# Sheet1.net
KiCad netlist of a schematic drawn in Altium Designer
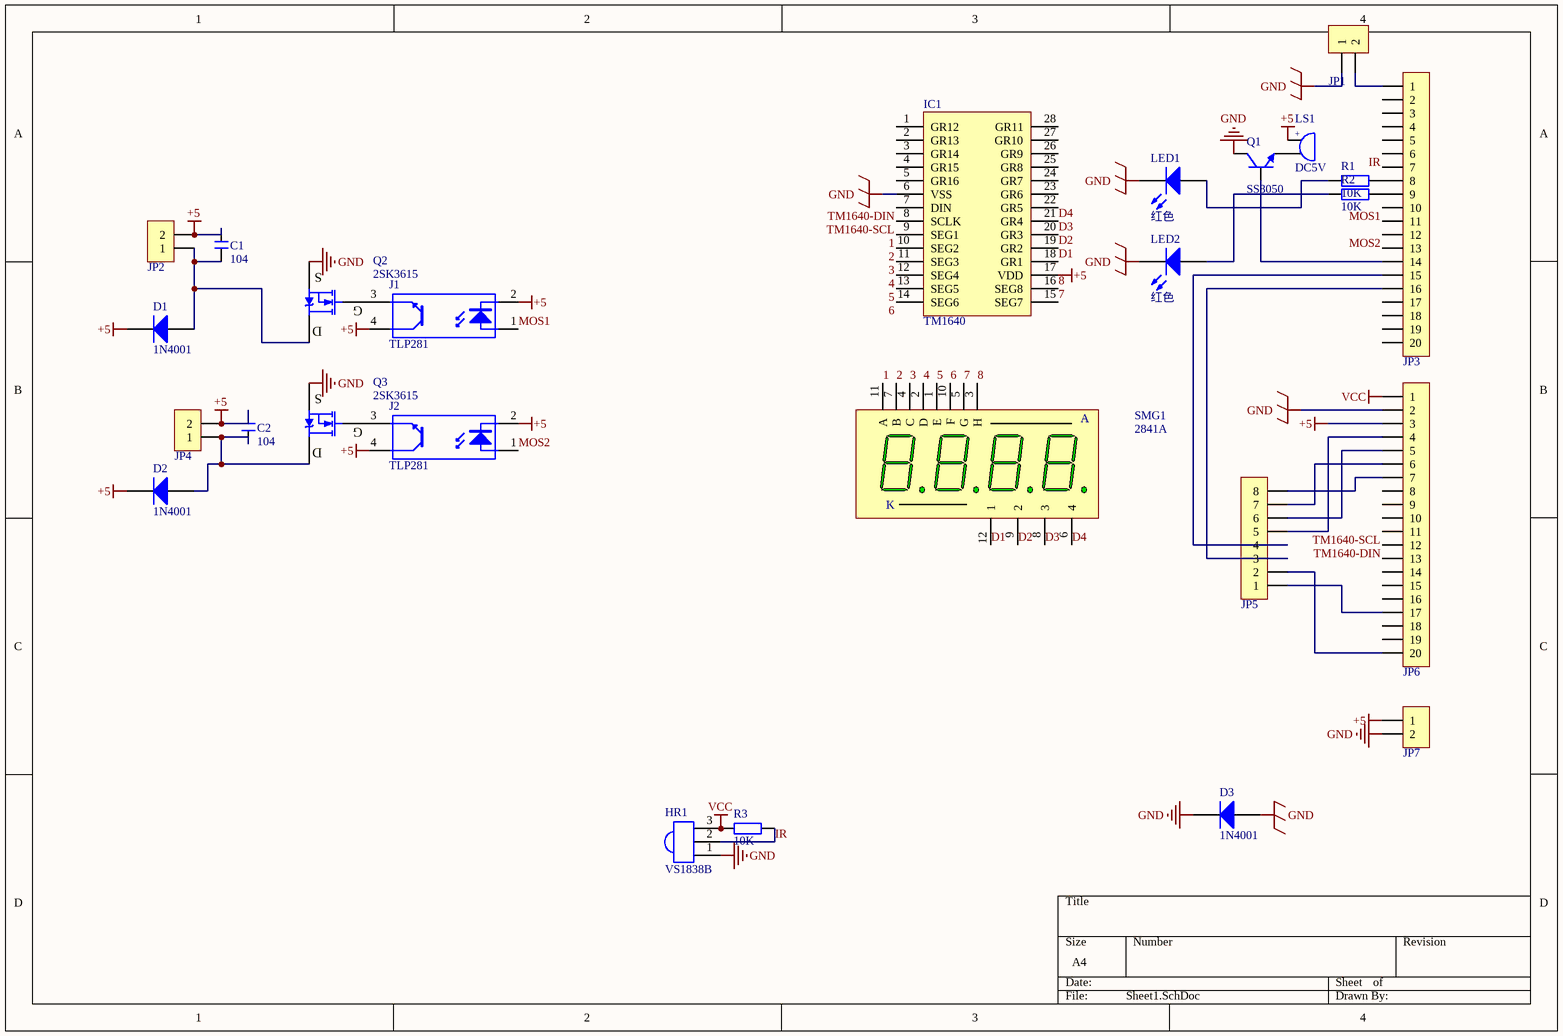
[diagram p0: Sheet1.SchDoc]

(export (version "E")
  (design (tool "Eeschema 10.0.6"))
  (components
    (comp (ref "C1")
      (value "104")
      (footprint "C 0805_L")
      (description "贴片电容")
      (libsource (lib "0.1 - 电阻-电容-电感") (part "C"))
    )
    (comp (ref "C2")
      (value "104")
      (footprint "C 0805_L")
      (description "贴片电容")
      (libsource (lib "0.1 - 电阻-电容-电感") (part "C"))
    )
    (comp (ref "D1")
      (value "Diode")
      (footprint "DIODE-AXL")
      (description "二极管")
      (fields (field (name "TYPE") "1N4001") (field (name "PUBLISHER") "Altium Limited"))
      (libsource (lib "0.2 -  二极管-整流桥") (part "Diode"))
    )
    (comp (ref "D2")
      (value "Diode")
      (footprint "DIODE-AXL")
      (description "二极管")
      (fields (field (name "TYPE") "1N4001") (field (name "PUBLISHER") "Altium Limited"))
      (libsource (lib "0.2 -  二极管-整流桥") (part "Diode"))
    )
    (comp (ref "D3")
      (value "Diode")
      (footprint "DIODE-AXL")
      (description "二极管")
      (fields (field (name "TYPE") "1N4001") (field (name "PUBLISHER") "Altium Limited"))
      (libsource (lib "0.2 -  二极管-整流桥") (part "Diode"))
    )
    (comp (ref "HR1")
      (value "VS1838B")
      (footprint "VS1838B-B")
      (description "红外接收头")
      (fields (field (name "版权归属") "封装库来自淘宝 ID：黄晶宝石"))
      (libsource (lib "1.2 - 传感元件") (part "VS1838B"))
    )
    (comp (ref "IC1")
      (value "TM1640")
      (footprint "SOP28_L")
      (description "LED驱动控制芯片")
      (fields (field (name "版权归属") "封装库来自淘宝 ID：黄晶宝石"))
      (libsource (lib "1.0 - 常见芯片") (part "TM1640"))
    )
    (comp (ref "J1")
      (value "TLP281")
      (footprint "2.50-DIP直插封装:DIP4-300")
      (description "光耦")
      (fields (field (name "PUBLISHER") "Altium Limited"))
      (libsource (lib "2.0 - 保险丝-晶振-光耦") (part "TLP281"))
    )
    (comp (ref "J2")
      (value "TLP281")
      (footprint "2.50-DIP直插封装:DIP4-300")
      (description "光耦")
      (fields (field (name "PUBLISHER") "Altium Limited"))
      (libsource (lib "2.0 - 保险丝-晶振-光耦") (part "TLP281"))
    )
    (comp (ref "JP1")
      (value "HDR-1X2")
      (footprint "HDR2.54-LI-2P")
      (description "2P接插件")
      (fields (field (name "版权归属") "封装库来自淘宝 ID：黄晶宝石"))
      (libsource (lib "5.3 - 接插件-脚距2.54 (100mil) ") (part "Header 2"))
    )
    (comp (ref "JP2")
      (value "HDR-1X2")
      (footprint "KF2EDGK5.08-LI-2P")
      (description "2P接插件")
      (fields (field (name "版权归属") "封装库来自淘宝卖家 ID：黄晶宝石"))
      (libsource (lib "") (part "Header 2_1"))
    )
    (comp (ref "JP3")
      (value "HDR-1X20")
      (footprint "HDR2.54-M-LI-20P")
      (description "20P接插件")
      (fields (field (name "版权归属") "封装库来自淘宝 ID：黄晶宝石"))
      (libsource (lib "5.3 - 接插件-脚距2.54 (100mil) ") (part "Header 20"))
    )
    (comp (ref "JP4")
      (value "HDR-1X2")
      (footprint "KF2EDGK5.08-LI-2P")
      (description "2P接插件")
      (fields (field (name "版权归属") "封装库来自淘宝卖家 ID：黄晶宝石"))
      (libsource (lib "") (part "Header 2_1"))
    )
    (comp (ref "JP5")
      (value "HDR-1X8")
      (footprint "HDR2.54-M-LI-8P")
      (description "8P接插件")
      (fields (field (name "版权归属") "封装库来自淘宝 ID：黄晶宝石"))
      (libsource (lib "5.3 - 接插件-脚距2.54 (100mil) ") (part "Header 8"))
    )
    (comp (ref "JP6")
      (value "HDR-1X20")
      (footprint "HDR2.54-M-LI-20P")
      (description "20P接插件")
      (fields (field (name "版权归属") "封装库来自淘宝 ID：黄晶宝石"))
      (libsource (lib "5.3 - 接插件-脚距2.54 (100mil) ") (part "Header 20"))
    )
    (comp (ref "JP7")
      (value "HDR-1X2")
      (footprint "KF2EDGK5.08-LI-2P")
      (description "2P接插件")
      (fields (field (name "版权归属") "封装库来自淘宝卖家 ID：黄晶宝石"))
      (libsource (lib "5.8 - 接插件-脚距5.08 (200mil) ") (part "Header 2"))
    )
    (comp (ref "LED1")
      (value "红色")
      (footprint "LED 3MM-B")
      (description "直插3mm LED")
      (fields (field (name "版权归属") "封装库来自淘宝 ID：黄晶宝石"))
      (libsource (lib "0.3 - LED发光二极管") (part "LED-3MM"))
    )
    (comp (ref "LED2")
      (value "红色")
      (footprint "LED 3MM-B")
      (description "直插3mm LED")
      (fields (field (name "版权归属") "封装库来自淘宝 ID：黄晶宝石"))
      (libsource (lib "0.3 - LED发光二极管") (part "LED-3MM"))
    )
    (comp (ref "LS1")
      (value "DC5V")
      (footprint "BEEP 5x9x5.5")
      (description "蜂鸣器")
      (fields (field (name "版权归属") "封装库来自淘宝 ID：黄晶宝石"))
      (libsource (lib "4.1 - 未分类器件") (part "BEEP"))
    )
    (comp (ref "Q1")
      (value "SS8050")
      (footprint "TO92A")
      (description "高频放大-NPN型")
      (fields (field (name "版权归属") "封装库来自淘宝 ID：黄晶宝石"))
      (libsource (lib "0.4 - 三极管") (part "8050-DIP"))
    )
    (comp (ref "Q2")
      (value "2SK3615")
      (footprint "TO252")
      (description "N沟场效应管")
      (libsource (lib "0.5 - 场效应管-可控硅") (part "2SK3615"))
    )
    (comp (ref "Q3")
      (value "2SK3615")
      (footprint "TO252")
      (description "N沟场效应管")
      (libsource (lib "0.5 - 场效应管-可控硅") (part "2SK3615"))
    )
    (comp (ref "R1")
      (value "10K")
      (footprint "R 0805_L")
      (description "贴片电阻")
      (fields (field (name "版权归属") "来自淘宝 ID：黄晶宝石"))
      (libsource (lib "0.1 - 电阻-电容-电感") (part "R"))
    )
    (comp (ref "R2")
      (value "10K")
      (footprint "R 0805_L")
      (description "贴片电阻")
      (fields (field (name "版权归属") "来自淘宝 ID：黄晶宝石"))
      (libsource (lib "0.1 - 电阻-电容-电感") (part "R"))
    )
    (comp (ref "R3")
      (value "10K")
      (footprint "R 0805_L")
      (description "贴片电阻")
      (fields (field (name "版权归属") "来自淘宝 ID：黄晶宝石"))
      (libsource (lib "0.1 - 电阻-电容-电感") (part "R"))
    )
    (comp (ref "SMG1")
      (value "2841A")
      (footprint "SMG 0.28-4P_B")
      (description "0.28寸4位共阴数码管")
      (fields (field (name "版权归属") "封装库来自淘宝 ID：黄晶宝石"))
      (libsource (lib "0.6 - 数码管-TFT屏") (part "2841A"))
    )
  )
  (nets
    (net (code "1") (name "+5") (class "Default")
      (node (ref "C1") (pin "2") (pinfunction "2_2") (pintype "passive"))
      (node (ref "C2") (pin "2") (pinfunction "2_2") (pintype "passive"))
      (node (ref "D1") (pin "2") (pinfunction "K_2") (pintype "passive"))
      (node (ref "D2") (pin "2") (pinfunction "K_2") (pintype "passive"))
      (node (ref "IC1") (pin "17") (pinfunction "VDD_17") (pintype "passive"))
      (node (ref "J1") (pin "2") (pinfunction "K_2") (pintype "passive"))
      (node (ref "J1") (pin "4") (pinfunction "C_4") (pintype "passive"))
      (node (ref "J2") (pin "2") (pinfunction "K_2") (pintype "passive"))
      (node (ref "J2") (pin "4") (pinfunction "C_4") (pintype "passive"))
      (node (ref "JP2") (pin "2") (pinfunction "2_2") (pintype "passive"))
      (node (ref "JP4") (pin "2") (pinfunction "2_2") (pintype "passive"))
      (node (ref "JP6") (pin "3") (pinfunction "3_3") (pintype "passive"))
      (node (ref "JP7") (pin "1") (pinfunction "1_1") (pintype "passive"))
      (node (ref "LS1") (pin "1") (pinfunction "1_1") (pintype "passive"))
    )
    (net (code "2") (name "/1") (class "Default")
      (node (ref "IC1") (pin "9") (pinfunction "SEG1_9") (pintype "passive"))
      (node (ref "SMG1") (pin "11") (pinfunction "A_11") (pintype "passive"))
    )
    (net (code "3") (name "/2") (class "Default")
      (node (ref "IC1") (pin "10") (pinfunction "SEG2_10") (pintype "passive"))
      (node (ref "SMG1") (pin "7") (pinfunction "B_7") (pintype "passive"))
    )
    (net (code "4") (name "/3") (class "Default")
      (node (ref "IC1") (pin "11") (pinfunction "SEG3_11") (pintype "passive"))
      (node (ref "SMG1") (pin "4") (pinfunction "C_4") (pintype "passive"))
    )
    (net (code "5") (name "/4") (class "Default")
      (node (ref "IC1") (pin "12") (pinfunction "SEG4_12") (pintype "passive"))
      (node (ref "SMG1") (pin "2") (pinfunction "D_2") (pintype "passive"))
    )
    (net (code "6") (name "/5") (class "Default")
      (node (ref "IC1") (pin "13") (pinfunction "SEG5_13") (pintype "passive"))
      (node (ref "SMG1") (pin "1") (pinfunction "E_1") (pintype "passive"))
    )
    (net (code "7") (name "/6") (class "Default")
      (node (ref "IC1") (pin "14") (pinfunction "SEG6_14") (pintype "passive"))
      (node (ref "SMG1") (pin "10") (pinfunction "F_10") (pintype "passive"))
    )
    (net (code "8") (name "/7") (class "Default")
      (node (ref "IC1") (pin "15") (pinfunction "SEG7_15") (pintype "passive"))
      (node (ref "SMG1") (pin "5") (pinfunction "G_5") (pintype "passive"))
    )
    (net (code "9") (name "/8") (class "Default")
      (node (ref "IC1") (pin "16") (pinfunction "SEG8_16") (pintype "passive"))
      (node (ref "SMG1") (pin "3") (pinfunction "H_3") (pintype "passive"))
    )
    (net (code "10") (name "/D1") (class "Default")
      (node (ref "IC1") (pin "18") (pinfunction "GR1_18") (pintype "passive"))
      (node (ref "SMG1") (pin "12") (pinfunction "1_12") (pintype "passive"))
    )
    (net (code "11") (name "/D2") (class "Default")
      (node (ref "IC1") (pin "19") (pinfunction "GR2_19") (pintype "passive"))
      (node (ref "SMG1") (pin "9") (pinfunction "2_9") (pintype "passive"))
    )
    (net (code "12") (name "/D3") (class "Default")
      (node (ref "IC1") (pin "20") (pinfunction "GR3_20") (pintype "passive"))
      (node (ref "SMG1") (pin "8") (pinfunction "3_8") (pintype "passive"))
    )
    (net (code "13") (name "/D4") (class "Default")
      (node (ref "IC1") (pin "21") (pinfunction "GR4_21") (pintype "passive"))
      (node (ref "SMG1") (pin "6") (pinfunction "4_6") (pintype "passive"))
    )
    (net (code "14") (name "/IR") (class "Default")
      (node (ref "HR1") (pin "2") (pinfunction "K_2") (pintype "passive"))
      (node (ref "JP3") (pin "6") (pinfunction "6_6") (pintype "passive"))
      (node (ref "R3") (pin "2") (pinfunction "2_2") (pintype "passive"))
    )
    (net (code "15") (name "/MOS1") (class "Default")
      (node (ref "J1") (pin "1") (pinfunction "A_1") (pintype "passive"))
      (node (ref "JP3") (pin "10") (pinfunction "10_10") (pintype "passive"))
    )
    (net (code "16") (name "/MOS2") (class "Default")
      (node (ref "J2") (pin "1") (pinfunction "A_1") (pintype "passive"))
      (node (ref "JP3") (pin "12") (pinfunction "12_12") (pintype "passive"))
    )
    (net (code "17") (name "/TM1640-DIN") (class "Default")
      (node (ref "IC1") (pin "7") (pinfunction "DIN_7") (pintype "passive"))
      (node (ref "JP6") (pin "12") (pinfunction "12_12") (pintype "passive"))
    )
    (net (code "18") (name "/TM1640-SCL") (class "Default")
      (node (ref "IC1") (pin "8") (pinfunction "SCLK_8") (pintype "passive"))
      (node (ref "JP6") (pin "11") (pinfunction "11_11") (pintype "passive"))
    )
    (net (code "19") (name "GND") (class "Default")
      (node (ref "D3") (pin "1") (pinfunction "A_1") (pintype "passive"))
      (node (ref "D3") (pin "2") (pinfunction "K_2") (pintype "passive"))
      (node (ref "HR1") (pin "1") (pinfunction "A_1") (pintype "passive"))
      (node (ref "IC1") (pin "6") (pinfunction "VSS_6") (pintype "passive"))
      (node (ref "JP1") (pin "1") (pinfunction "1_1") (pintype "passive"))
      (node (ref "JP6") (pin "2") (pinfunction "2_2") (pintype "passive"))
      (node (ref "JP7") (pin "2") (pinfunction "2_2") (pintype "passive"))
      (node (ref "LED1") (pin "2") (pinfunction "K_2") (pintype "passive"))
      (node (ref "LED2") (pin "2") (pinfunction "K_2") (pintype "passive"))
      (node (ref "Q1") (pin "3") (pinfunction "C_3") (pintype "passive"))
      (node (ref "Q2") (pin "3") (pinfunction "S_3") (pintype "passive"))
      (node (ref "Q3") (pin "3") (pinfunction "S_3") (pintype "passive"))
    )
    (net (code "20") (name "Net-(D1-A)") (class "Default")
      (node (ref "C1") (pin "1") (pinfunction "1_1") (pintype "passive"))
      (node (ref "D1") (pin "1") (pinfunction "A_1") (pintype "passive"))
      (node (ref "JP2") (pin "1") (pinfunction "1_1") (pintype "passive"))
      (node (ref "Q2") (pin "2") (pinfunction "D_2") (pintype "passive"))
    )
    (net (code "21") (name "Net-(D2-A)") (class "Default")
      (node (ref "C2") (pin "1") (pinfunction "1_1") (pintype "passive"))
      (node (ref "D2") (pin "1") (pinfunction "A_1") (pintype "passive"))
      (node (ref "JP4") (pin "1") (pinfunction "1_1") (pintype "passive"))
      (node (ref "Q3") (pin "2") (pinfunction "D_2") (pintype "passive"))
    )
    (net (code "22") (name "Net-(J1-E)") (class "Default")
      (node (ref "J1") (pin "3") (pinfunction "E_3") (pintype "passive"))
      (node (ref "Q2") (pin "1") (pinfunction "G_1") (pintype "passive"))
    )
    (net (code "23") (name "Net-(J2-E)") (class "Default")
      (node (ref "J2") (pin "3") (pinfunction "E_3") (pintype "passive"))
      (node (ref "Q3") (pin "1") (pinfunction "G_1") (pintype "passive"))
    )
    (net (code "24") (name "Net-(JP1-Pad2)") (class "Default")
      (node (ref "JP1") (pin "2") (pinfunction "2_2") (pintype "passive"))
      (node (ref "JP3") (pin "1") (pinfunction "1_1") (pintype "passive"))
    )
    (net (code "25") (name "Net-(JP3-Pad8)") (class "Default")
      (node (ref "JP3") (pin "8") (pinfunction "8_8") (pintype "passive"))
      (node (ref "R1") (pin "2") (pinfunction "2_2") (pintype "passive"))
    )
    (net (code "26") (name "Net-(JP3-Pad9)") (class "Default")
      (node (ref "JP3") (pin "9") (pinfunction "9_9") (pintype "passive"))
      (node (ref "R2") (pin "2") (pinfunction "2_2") (pintype "passive"))
    )
    (net (code "27") (name "Net-(JP3-Pad15)") (class "Default")
      (node (ref "JP3") (pin "15") (pinfunction "15_15") (pintype "passive"))
      (node (ref "JP5") (pin "4") (pinfunction "4_4") (pintype "passive"))
    )
    (net (code "28") (name "Net-(JP3-Pad16)") (class "Default")
      (node (ref "JP3") (pin "16") (pinfunction "16_16") (pintype "passive"))
      (node (ref "JP5") (pin "3") (pinfunction "3_3") (pintype "passive"))
    )
    (net (code "29") (name "Net-(JP5-Pad1)") (class "Default")
      (node (ref "JP5") (pin "1") (pinfunction "1_1") (pintype "passive"))
      (node (ref "JP6") (pin "17") (pinfunction "17_17") (pintype "passive"))
    )
    (net (code "30") (name "Net-(JP5-Pad2)") (class "Default")
      (node (ref "JP5") (pin "2") (pinfunction "2_2") (pintype "passive"))
      (node (ref "JP6") (pin "20") (pinfunction "20_20") (pintype "passive"))
    )
    (net (code "31") (name "Net-(JP5-Pad5)") (class "Default")
      (node (ref "JP5") (pin "5") (pinfunction "5_5") (pintype "passive"))
      (node (ref "JP6") (pin "4") (pinfunction "4_4") (pintype "passive"))
    )
    (net (code "32") (name "Net-(JP5-Pad6)") (class "Default")
      (node (ref "JP5") (pin "6") (pinfunction "6_6") (pintype "passive"))
      (node (ref "JP6") (pin "5") (pinfunction "5_5") (pintype "passive"))
    )
    (net (code "33") (name "Net-(JP5-Pad7)") (class "Default")
      (node (ref "JP5") (pin "7") (pinfunction "7_7") (pintype "passive"))
      (node (ref "JP6") (pin "6") (pinfunction "6_6") (pintype "passive"))
    )
    (net (code "34") (name "Net-(JP5-Pad8)") (class "Default")
      (node (ref "JP5") (pin "8") (pinfunction "8_8") (pintype "passive"))
      (node (ref "JP6") (pin "7") (pinfunction "7_7") (pintype "passive"))
    )
    (net (code "35") (name "Net-(LED1-A)") (class "Default")
      (node (ref "LED1") (pin "1") (pinfunction "A_1") (pintype "passive"))
      (node (ref "R1") (pin "1") (pinfunction "1_1") (pintype "passive"))
    )
    (net (code "36") (name "Net-(LED2-A)") (class "Default")
      (node (ref "LED2") (pin "1") (pinfunction "A_1") (pintype "passive"))
      (node (ref "R2") (pin "1") (pinfunction "1_1") (pintype "passive"))
    )
    (net (code "37") (name "Net-(Q1-B)") (class "Default")
      (node (ref "JP3") (pin "14") (pinfunction "14_14") (pintype "passive"))
      (node (ref "Q1") (pin "2") (pinfunction "B_2") (pintype "passive"))
    )
    (net (code "38") (name "Net-(Q1-E)") (class "Default")
      (node (ref "LS1") (pin "2") (pinfunction "2_2") (pintype "passive"))
      (node (ref "Q1") (pin "1") (pinfunction "E_1") (pintype "passive"))
    )
    (net (code "39") (name "VCC") (class "Default")
      (node (ref "HR1") (pin "3") (pinfunction "E_3") (pintype "passive"))
      (node (ref "JP6") (pin "1") (pinfunction "1_1") (pintype "passive"))
      (node (ref "R3") (pin "1") (pinfunction "1_1") (pintype "passive"))
    )
    (net (code "40") (name "unconnected-(IC1-GR5-Pad22)") (class "Default")
      (node (ref "IC1") (pin "22") (pinfunction "GR5_22") (pintype "passive"))
    )
    (net (code "41") (name "unconnected-(IC1-GR6-Pad23)") (class "Default")
      (node (ref "IC1") (pin "23") (pinfunction "GR6_23") (pintype "passive"))
    )
    (net (code "42") (name "unconnected-(IC1-GR7-Pad24)") (class "Default")
      (node (ref "IC1") (pin "24") (pinfunction "GR7_24") (pintype "passive"))
    )
    (net (code "43") (name "unconnected-(IC1-GR8-Pad25)") (class "Default")
      (node (ref "IC1") (pin "25") (pinfunction "GR8_25") (pintype "passive"))
    )
    (net (code "44") (name "unconnected-(IC1-GR9-Pad26)") (class "Default")
      (node (ref "IC1") (pin "26") (pinfunction "GR9_26") (pintype "passive"))
    )
    (net (code "45") (name "unconnected-(IC1-GR10-Pad27)") (class "Default")
      (node (ref "IC1") (pin "27") (pinfunction "GR10_27") (pintype "passive"))
    )
    (net (code "46") (name "unconnected-(IC1-GR11-Pad28)") (class "Default")
      (node (ref "IC1") (pin "28") (pinfunction "GR11_28") (pintype "passive"))
    )
    (net (code "47") (name "unconnected-(IC1-GR12-Pad1)") (class "Default")
      (node (ref "IC1") (pin "1") (pinfunction "GR12_1") (pintype "passive"))
    )
    (net (code "48") (name "unconnected-(IC1-GR13-Pad2)") (class "Default")
      (node (ref "IC1") (pin "2") (pinfunction "GR13_2") (pintype "passive"))
    )
    (net (code "49") (name "unconnected-(IC1-GR14-Pad3)") (class "Default")
      (node (ref "IC1") (pin "3") (pinfunction "GR14_3") (pintype "passive"))
    )
    (net (code "50") (name "unconnected-(IC1-GR15-Pad4)") (class "Default")
      (node (ref "IC1") (pin "4") (pinfunction "GR15_4") (pintype "passive"))
    )
    (net (code "51") (name "unconnected-(IC1-GR16-Pad5)") (class "Default")
      (node (ref "IC1") (pin "5") (pinfunction "GR16_5") (pintype "passive"))
    )
    (net (code "52") (name "unconnected-(JP3-Pad2)") (class "Default")
      (node (ref "JP3") (pin "2") (pinfunction "2_2") (pintype "passive"))
    )
    (net (code "53") (name "unconnected-(JP3-Pad3)") (class "Default")
      (node (ref "JP3") (pin "3") (pinfunction "3_3") (pintype "passive"))
    )
    (net (code "54") (name "unconnected-(JP3-Pad4)") (class "Default")
      (node (ref "JP3") (pin "4") (pinfunction "4_4") (pintype "passive"))
    )
    (net (code "55") (name "unconnected-(JP3-Pad5)") (class "Default")
      (node (ref "JP3") (pin "5") (pinfunction "5_5") (pintype "passive"))
    )
    (net (code "56") (name "unconnected-(JP3-Pad7)") (class "Default")
      (node (ref "JP3") (pin "7") (pinfunction "7_7") (pintype "passive"))
    )
    (net (code "57") (name "unconnected-(JP3-Pad11)") (class "Default")
      (node (ref "JP3") (pin "11") (pinfunction "11_11") (pintype "passive"))
    )
    (net (code "58") (name "unconnected-(JP3-Pad13)") (class "Default")
      (node (ref "JP3") (pin "13") (pinfunction "13_13") (pintype "passive"))
    )
    (net (code "59") (name "unconnected-(JP3-Pad17)") (class "Default")
      (node (ref "JP3") (pin "17") (pinfunction "17_17") (pintype "passive"))
    )
    (net (code "60") (name "unconnected-(JP3-Pad18)") (class "Default")
      (node (ref "JP3") (pin "18") (pinfunction "18_18") (pintype "passive"))
    )
    (net (code "61") (name "unconnected-(JP3-Pad19)") (class "Default")
      (node (ref "JP3") (pin "19") (pinfunction "19_19") (pintype "passive"))
    )
    (net (code "62") (name "unconnected-(JP3-Pad20)") (class "Default")
      (node (ref "JP3") (pin "20") (pinfunction "20_20") (pintype "passive"))
    )
    (net (code "63") (name "unconnected-(JP6-Pad8)") (class "Default")
      (node (ref "JP6") (pin "8") (pinfunction "8_8") (pintype "passive"))
    )
    (net (code "64") (name "unconnected-(JP6-Pad9)") (class "Default")
      (node (ref "JP6") (pin "9") (pinfunction "9_9") (pintype "passive"))
    )
    (net (code "65") (name "unconnected-(JP6-Pad10)") (class "Default")
      (node (ref "JP6") (pin "10") (pinfunction "10_10") (pintype "passive"))
    )
    (net (code "66") (name "unconnected-(JP6-Pad13)") (class "Default")
      (node (ref "JP6") (pin "13") (pinfunction "13_13") (pintype "passive"))
    )
    (net (code "67") (name "unconnected-(JP6-Pad14)") (class "Default")
      (node (ref "JP6") (pin "14") (pinfunction "14_14") (pintype "passive"))
    )
    (net (code "68") (name "unconnected-(JP6-Pad15)") (class "Default")
      (node (ref "JP6") (pin "15") (pinfunction "15_15") (pintype "passive"))
    )
    (net (code "69") (name "unconnected-(JP6-Pad16)") (class "Default")
      (node (ref "JP6") (pin "16") (pinfunction "16_16") (pintype "passive"))
    )
    (net (code "70") (name "unconnected-(JP6-Pad18)") (class "Default")
      (node (ref "JP6") (pin "18") (pinfunction "18_18") (pintype "passive"))
    )
    (net (code "71") (name "unconnected-(JP6-Pad19)") (class "Default")
      (node (ref "JP6") (pin "19") (pinfunction "19_19") (pintype "passive"))
    )
  )
)
